# Top.net
KiCad netlist of a schematic drawn in Altium Designer
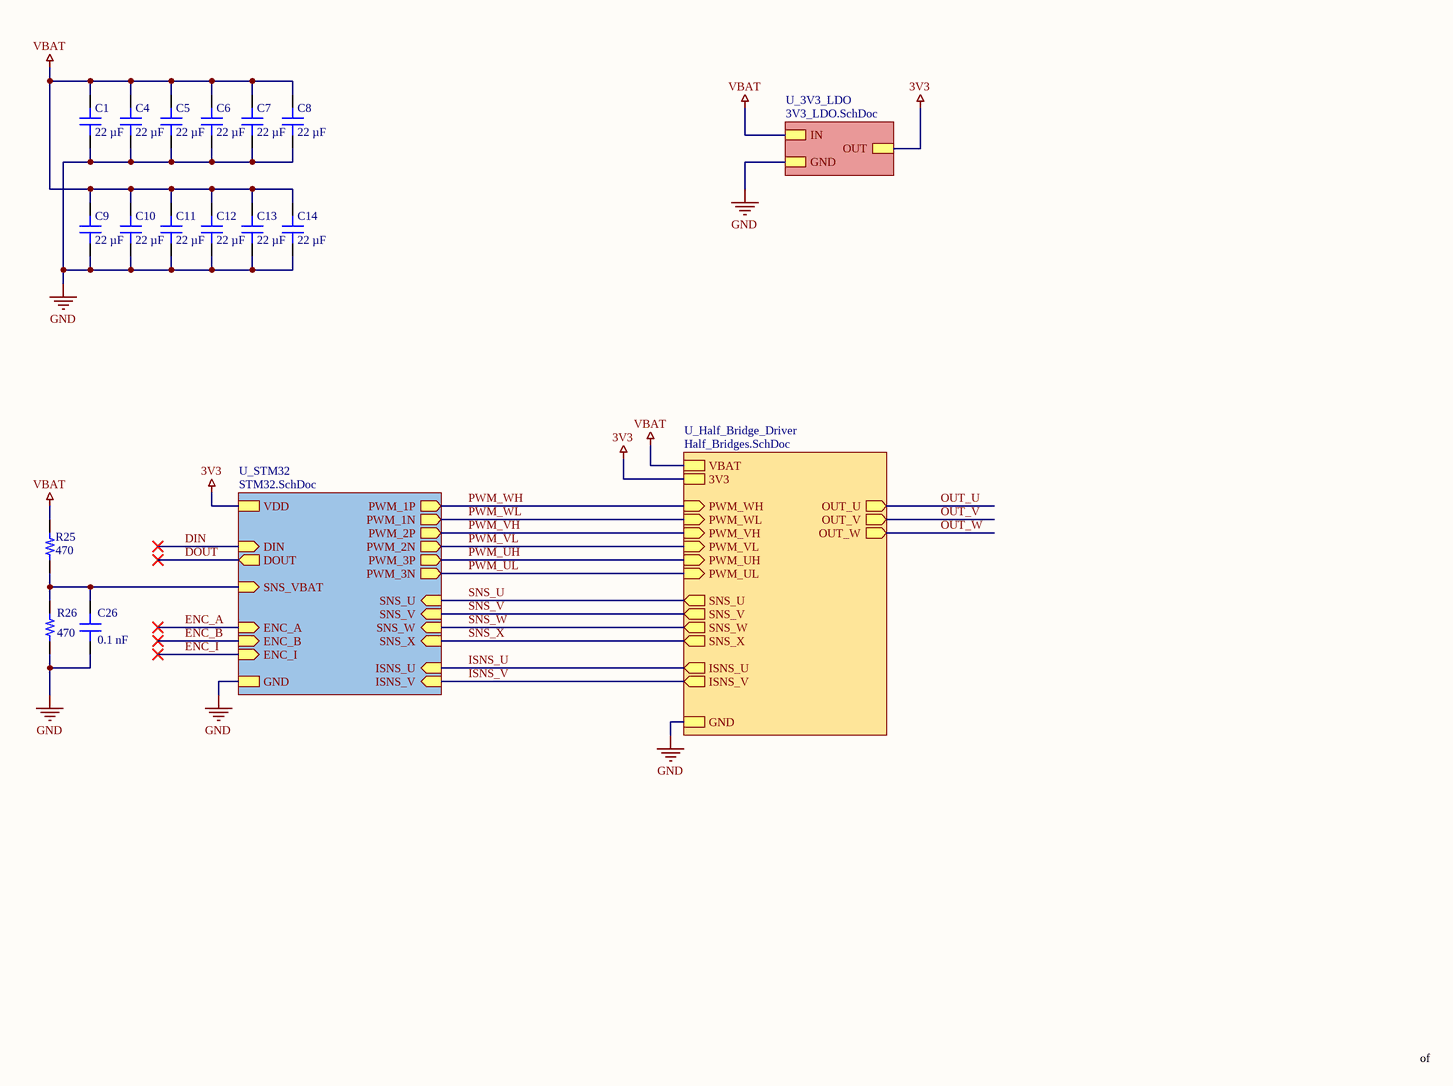
[diagram p0: Top.SchDoc]

(export (version "E")
  (design (tool "Eeschema 10.0.6"))
  (components
    (comp (ref "C1")
      (value "22 µF")
      (footprint "CAP 0805_2012")
      (description "CAP CER 22UF 25V X5R 0805")
      (fields (field (name "PART NUMBER") "CC0805MKX5R8BB226") (field (name "MANUFACTURER") "Yageo"))
      (libsource (lib "Celestial Altium Library - altium_library") (part "Capacitor"))
    )
    (comp (ref "C4")
      (value "22 µF")
      (footprint "CAP 0805_2012")
      (description "CAP CER 22UF 25V X5R 0805")
      (fields (field (name "PART NUMBER") "CC0805MKX5R8BB226") (field (name "MANUFACTURER") "Yageo"))
      (libsource (lib "Celestial Altium Library - altium_library") (part "Capacitor"))
    )
    (comp (ref "C5")
      (value "22 µF")
      (footprint "CAP 0805_2012")
      (description "CAP CER 22UF 25V X5R 0805")
      (fields (field (name "PART NUMBER") "CC0805MKX5R8BB226") (field (name "MANUFACTURER") "Yageo"))
      (libsource (lib "Celestial Altium Library - altium_library") (part "Capacitor"))
    )
    (comp (ref "C6")
      (value "22 µF")
      (footprint "CAP 0805_2012")
      (description "CAP CER 22UF 25V X5R 0805")
      (fields (field (name "PART NUMBER") "CC0805MKX5R8BB226") (field (name "MANUFACTURER") "Yageo"))
      (libsource (lib "Celestial Altium Library - altium_library") (part "Capacitor"))
    )
    (comp (ref "C7")
      (value "22 µF")
      (footprint "CAP 0805_2012")
      (description "CAP CER 22UF 25V X5R 0805")
      (fields (field (name "PART NUMBER") "CC0805MKX5R8BB226") (field (name "MANUFACTURER") "Yageo"))
      (libsource (lib "Celestial Altium Library - altium_library") (part "Capacitor"))
    )
    (comp (ref "C8")
      (value "22 µF")
      (footprint "CAP 0805_2012")
      (description "CAP CER 22UF 25V X5R 0805")
      (fields (field (name "PART NUMBER") "CC0805MKX5R8BB226") (field (name "MANUFACTURER") "Yageo"))
      (libsource (lib "Celestial Altium Library - altium_library") (part "Capacitor"))
    )
    (comp (ref "C9")
      (value "22 µF")
      (footprint "CAP 0805_2012")
      (description "CAP CER 22UF 25V X5R 0805")
      (fields (field (name "PART NUMBER") "CC0805MKX5R8BB226") (field (name "MANUFACTURER") "Yageo"))
      (libsource (lib "Celestial Altium Library - altium_library") (part "Capacitor"))
    )
    (comp (ref "C10")
      (value "22 µF")
      (footprint "CAP 0805_2012")
      (description "CAP CER 22UF 25V X5R 0805")
      (fields (field (name "PART NUMBER") "CC0805MKX5R8BB226") (field (name "MANUFACTURER") "Yageo"))
      (libsource (lib "Celestial Altium Library - altium_library") (part "Capacitor"))
    )
    (comp (ref "C11")
      (value "22 µF")
      (footprint "CAP 0805_2012")
      (description "CAP CER 22UF 25V X5R 0805")
      (fields (field (name "PART NUMBER") "CC0805MKX5R8BB226") (field (name "MANUFACTURER") "Yageo"))
      (libsource (lib "Celestial Altium Library - altium_library") (part "Capacitor"))
    )
    (comp (ref "C12")
      (value "22 µF")
      (footprint "CAP 0805_2012")
      (description "CAP CER 22UF 25V X5R 0805")
      (fields (field (name "PART NUMBER") "CC0805MKX5R8BB226") (field (name "MANUFACTURER") "Yageo"))
      (libsource (lib "Celestial Altium Library - altium_library") (part "Capacitor"))
    )
    (comp (ref "C13")
      (value "22 µF")
      (footprint "CAP 0805_2012")
      (description "CAP CER 22UF 25V X5R 0805")
      (fields (field (name "PART NUMBER") "CC0805MKX5R8BB226") (field (name "MANUFACTURER") "Yageo"))
      (libsource (lib "Celestial Altium Library - altium_library") (part "Capacitor"))
    )
    (comp (ref "C14")
      (value "22 µF")
      (footprint "CAP 0805_2012")
      (description "CAP CER 22UF 25V X5R 0805")
      (fields (field (name "PART NUMBER") "CC0805MKX5R8BB226") (field (name "MANUFACTURER") "Yageo"))
      (libsource (lib "Celestial Altium Library - altium_library") (part "Capacitor"))
    )
    (comp (ref "C26")
      (value "0.1 nF")
      (footprint "CAP 0402_1005")
      (description "CAP CER 0.1UF 16V X7R 0402")
      (fields (field (name "PART NUMBER") "C0402C104K4RACAUTO") (field (name "MANUFACTURER") "KEMET"))
      (libsource (lib "Celestial Altium Library - altium_library") (part "Capacitor"))
    )
    (comp (ref "R25")
      (value "470")
      (footprint "RES 0402_1005")
      (description "RES 14.3K OHM 1% 1/10W 0402")
      (fields
        (field (name "PART NUMBER") "RK73H1ETTP1432F")
        (field (name "MANUFACTURER") "KOA Speer Electronics, Inc.")
      )
      (libsource (lib "Celestial Altium Library - altium_library") (part "Resistor"))
    )
    (comp (ref "R26")
      (value "470")
      (footprint "RES 0402_1005")
      (description "RES 14.3K OHM 1% 1/10W 0402")
      (fields
        (field (name "PART NUMBER") "RK73H1ETTP1432F")
        (field (name "MANUFACTURER") "KOA Speer Electronics, Inc.")
      )
      (libsource (lib "Celestial Altium Library - altium_library") (part "Resistor"))
    )
  )
  (nets
    (net (code "19") (name "/SNS_VBAT") (class "Default")
      (node (ref "C26") (pin "2") (pinfunction "2_2") (pintype "passive"))
      (node (ref "R25") (pin "1") (pinfunction "1_1") (pintype "passive"))
      (node (ref "R26") (pin "2") (pinfunction "2_2") (pintype "passive"))
    )
    (net (code "23") (name "GND") (class "Default")
      (node (ref "C1") (pin "1") (pinfunction "1_1") (pintype "passive"))
      (node (ref "C10") (pin "1") (pinfunction "1_1") (pintype "passive"))
      (node (ref "C11") (pin "1") (pinfunction "1_1") (pintype "passive"))
      (node (ref "C12") (pin "1") (pinfunction "1_1") (pintype "passive"))
      (node (ref "C13") (pin "1") (pinfunction "1_1") (pintype "passive"))
      (node (ref "C14") (pin "1") (pinfunction "1_1") (pintype "passive"))
      (node (ref "C26") (pin "1") (pinfunction "1_1") (pintype "passive"))
      (node (ref "C4") (pin "1") (pinfunction "1_1") (pintype "passive"))
      (node (ref "C5") (pin "1") (pinfunction "1_1") (pintype "passive"))
      (node (ref "C6") (pin "1") (pinfunction "1_1") (pintype "passive"))
      (node (ref "C7") (pin "1") (pinfunction "1_1") (pintype "passive"))
      (node (ref "C8") (pin "1") (pinfunction "1_1") (pintype "passive"))
      (node (ref "C9") (pin "1") (pinfunction "1_1") (pintype "passive"))
      (node (ref "R26") (pin "1") (pinfunction "1_1") (pintype "passive"))
    )
    (net (code "24") (name "VBAT") (class "Default")
      (node (ref "C1") (pin "2") (pinfunction "2_2") (pintype "passive"))
      (node (ref "C10") (pin "2") (pinfunction "2_2") (pintype "passive"))
      (node (ref "C11") (pin "2") (pinfunction "2_2") (pintype "passive"))
      (node (ref "C12") (pin "2") (pinfunction "2_2") (pintype "passive"))
      (node (ref "C13") (pin "2") (pinfunction "2_2") (pintype "passive"))
      (node (ref "C14") (pin "2") (pinfunction "2_2") (pintype "passive"))
      (node (ref "C4") (pin "2") (pinfunction "2_2") (pintype "passive"))
      (node (ref "C5") (pin "2") (pinfunction "2_2") (pintype "passive"))
      (node (ref "C6") (pin "2") (pinfunction "2_2") (pintype "passive"))
      (node (ref "C7") (pin "2") (pinfunction "2_2") (pintype "passive"))
      (node (ref "C8") (pin "2") (pinfunction "2_2") (pintype "passive"))
      (node (ref "C9") (pin "2") (pinfunction "2_2") (pintype "passive"))
      (node (ref "R25") (pin "2") (pinfunction "2_2") (pintype "passive"))
    )
  )
)
